# MainShunt.net
KiCad netlist of a schematic drawn in Altium Designer
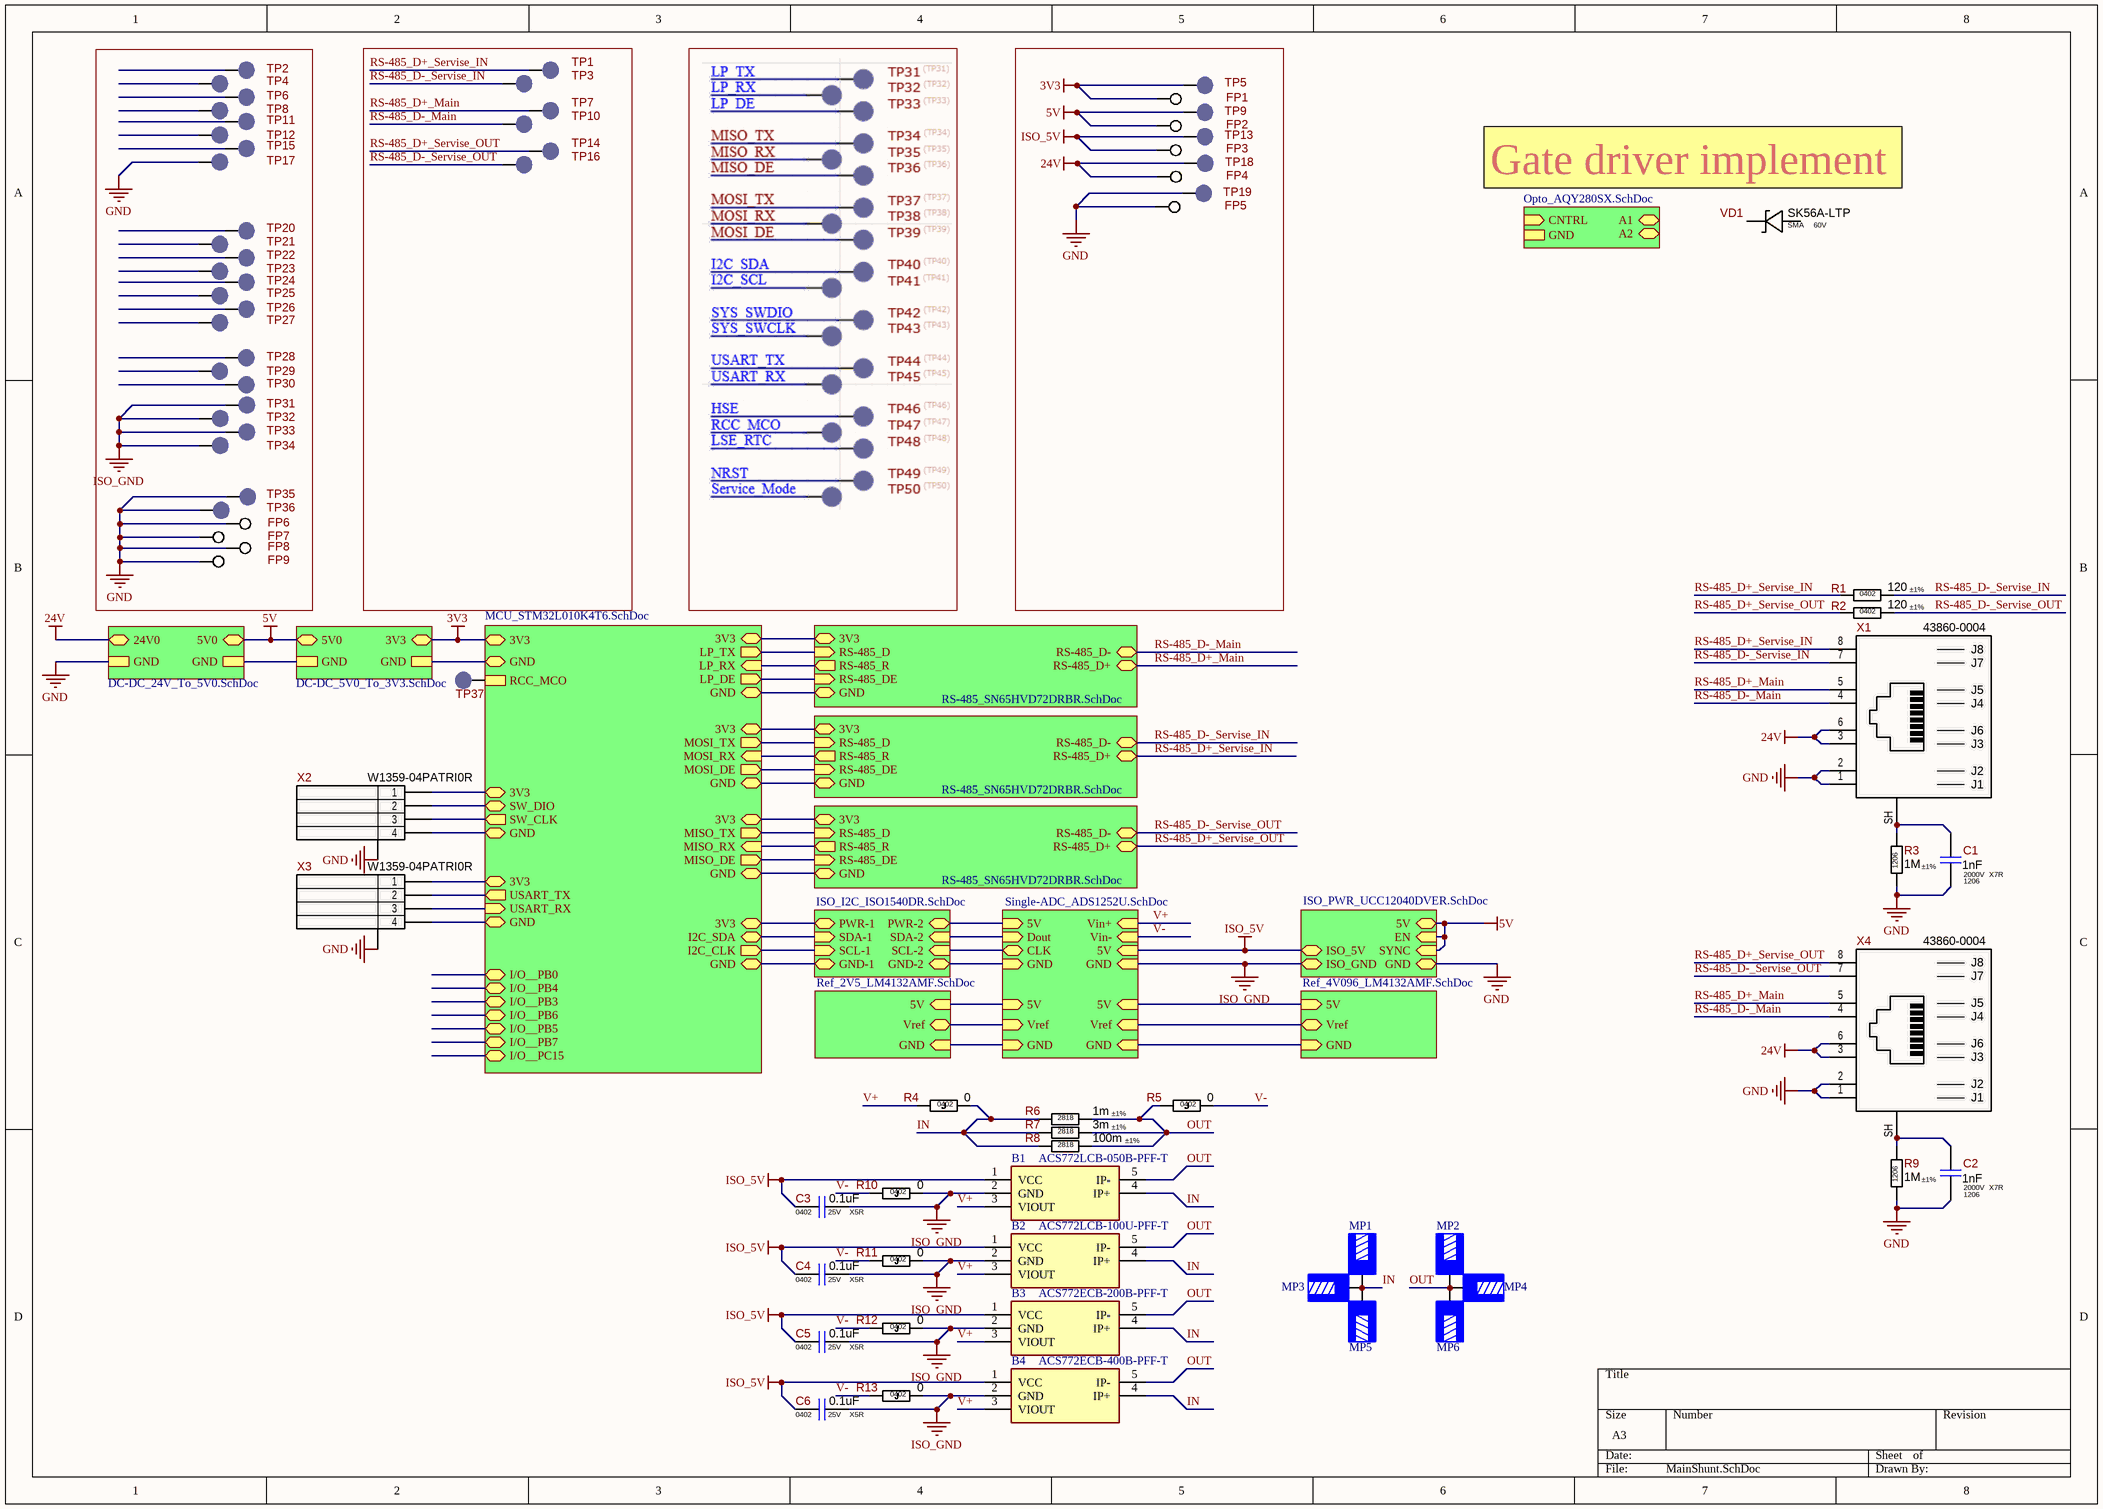
[diagram p0: MainShunt.SchDoc]

(export (version "E")
  (design (tool "Eeschema 10.0.6"))
  (components
    (comp (ref "B1")
      (value "ACS772LCB-050B-PFF-T")
      (footprint "ACS772KCB_XXX_PFF_T")
      (libsource (lib "EL.XXX.T01") (part "ACS772LCB-050B-PFF-T"))
    )
    (comp (ref "B2")
      (value "ACS772LCB-100U-PFF-T")
      (footprint "ACS772KCB_XXX_SMT_T")
      (libsource (lib "EL.XXX.T01") (part "ACS772LCB-100U-PFF-T"))
    )
    (comp (ref "B3")
      (value "ACS772ECB-200B-PFF-T")
      (footprint "ACS772KCB_XXX_PFF_T")
      (libsource (lib "EL.XXX.T01") (part "ACS772ECB-200B-PFF-T"))
    )
    (comp (ref "B4")
      (value "ACS772ECB-400B-PFF-T")
      (footprint "ACS772KCB_XXX_PFF_T")
      (libsource (lib "EL.XXX.T01") (part "ACS772ECB-400B-PFF-T"))
    )
    (comp (ref "C1")
      (value "1nF")
      (footprint "CAP-1206(3216)X125T20")
      (description "1nF 2000V X7R ±10% 1206 Ceramic Capacitor RoHS")
      (fields
        (field (name "PACKAGE") "1206")
        (field (name "VOLTAGE") "2000V")
        (field (name "DIELECTRIC TYPE") "X7R")
        (field (name "PART NUMBER") "CC1206KKX7RDBB102")
        (field (name "MANUFACTURER") "Yageo")
      )
      (libsource (lib "EL.XXX.T01") (part "Capacitor-NonPolar"))
    )
    (comp (ref "C2")
      (value "1nF")
      (footprint "CAP-1206(3216)X125T20")
      (description "1nF 2000V X7R ±10% 1206 Ceramic Capacitor RoHS")
      (fields
        (field (name "PACKAGE") "1206")
        (field (name "VOLTAGE") "2000V")
        (field (name "DIELECTRIC TYPE") "X7R")
        (field (name "PART NUMBER") "CC1206KKX7RDBB102")
        (field (name "MANUFACTURER") "Yageo")
      )
      (libsource (lib "EL.XXX.T01") (part "Capacitor-NonPolar"))
    )
    (comp (ref "C3")
      (value "0.1uF")
      (footprint "C_CERAMIC_0402_MED")
      (description "100nF 25V X5R ±10% 0402 Ceramic Capacitor RoHS")
      (fields
        (field (name "PART NUMBER") "CL05A104KA5NNNC")
        (field (name "MANUFACTURER") "Samsung Electro-Mechanics")
        (field (name "PACKAGE") "0402")
        (field (name "VOLTAGE") "25V")
        (field (name "DIELECTRIC TYPE") "X5R")
      )
      (libsource (lib "EL.XXX.T01") (part "CL05A104KA5NNNC"))
    )
    (comp (ref "C4")
      (value "0.1uF")
      (footprint "C_CERAMIC_0402_MED")
      (description "100nF 25V X5R ±10% 0402 Ceramic Capacitor RoHS")
      (fields
        (field (name "PART NUMBER") "CL05A104KA5NNNC")
        (field (name "MANUFACTURER") "Samsung Electro-Mechanics")
        (field (name "PACKAGE") "0402")
        (field (name "VOLTAGE") "25V")
        (field (name "DIELECTRIC TYPE") "X5R")
      )
      (libsource (lib "EL.XXX.T01") (part "CL05A104KA5NNNC"))
    )
    (comp (ref "C5")
      (value "0.1uF")
      (footprint "C_CERAMIC_0402_MED")
      (description "100nF 25V X5R ±10% 0402 Ceramic Capacitor RoHS")
      (fields
        (field (name "PART NUMBER") "CL05A104KA5NNNC")
        (field (name "MANUFACTURER") "Samsung Electro-Mechanics")
        (field (name "PACKAGE") "0402")
        (field (name "VOLTAGE") "25V")
        (field (name "DIELECTRIC TYPE") "X5R")
      )
      (libsource (lib "EL.XXX.T01") (part "CL05A104KA5NNNC"))
    )
    (comp (ref "C6")
      (value "0.1uF")
      (footprint "C_CERAMIC_0402_MED")
      (description "100nF 25V X5R ±10% 0402 Ceramic Capacitor RoHS")
      (fields
        (field (name "PART NUMBER") "CL05A104KA5NNNC")
        (field (name "MANUFACTURER") "Samsung Electro-Mechanics")
        (field (name "PACKAGE") "0402")
        (field (name "VOLTAGE") "25V")
        (field (name "DIELECTRIC TYPE") "X5R")
      )
      (libsource (lib "EL.XXX.T01") (part "CL05A104KA5NNNC"))
    )
    (comp (ref "FP1")
      (value "PAD-1.1mm")
      (footprint "PAD-1.1mm")
      (description "1.1mm Pad for Plug-In or Receptacle")
      (fields (field (name "MANUFACTURER") "NONE"))
      (libsource (lib "EL.XXX.T01") (part "Pad"))
    )
    (comp (ref "FP2")
      (value "PAD-1.1mm")
      (footprint "PAD-1.1mm")
      (description "1.1mm Pad for Plug-In or Receptacle")
      (fields (field (name "MANUFACTURER") "NONE"))
      (libsource (lib "EL.XXX.T01") (part "Pad"))
    )
    (comp (ref "FP3")
      (value "PAD-1.1mm")
      (footprint "PAD-1.1mm")
      (description "1.1mm Pad for Plug-In or Receptacle")
      (fields (field (name "MANUFACTURER") "NONE"))
      (libsource (lib "EL.XXX.T01") (part "Pad"))
    )
    (comp (ref "FP4")
      (value "PAD-1.1mm")
      (footprint "PAD-1.1mm")
      (description "1.1mm Pad for Plug-In or Receptacle")
      (fields (field (name "MANUFACTURER") "NONE"))
      (libsource (lib "EL.XXX.T01") (part "Pad"))
    )
    (comp (ref "FP5")
      (value "PAD-1.1mm")
      (footprint "PAD-1.1mm")
      (description "1.1mm Pad for Plug-In or Receptacle")
      (fields (field (name "MANUFACTURER") "NONE"))
      (libsource (lib "EL.XXX.T01") (part "Pad"))
    )
    (comp (ref "FP6")
      (value "PAD-1.1mm")
      (footprint "PAD-1.1mm")
      (description "1.1mm Pad for Plug-In or Receptacle")
      (fields (field (name "MANUFACTURER") "NONE"))
      (libsource (lib "EL.XXX.T01") (part "Pad"))
    )
    (comp (ref "FP7")
      (value "PAD-1.1mm")
      (footprint "PAD-1.1mm")
      (description "1.1mm Pad for Plug-In or Receptacle")
      (fields (field (name "MANUFACTURER") "NONE"))
      (libsource (lib "EL.XXX.T01") (part "Pad"))
    )
    (comp (ref "FP8")
      (value "PAD-1.1mm")
      (footprint "PAD-1.1mm")
      (description "1.1mm Pad for Plug-In or Receptacle")
      (fields (field (name "MANUFACTURER") "NONE"))
      (libsource (lib "EL.XXX.T01") (part "Pad"))
    )
    (comp (ref "FP9")
      (value "PAD-1.1mm")
      (footprint "PAD-1.1mm")
      (description "1.1mm Pad for Plug-In or Receptacle")
      (fields (field (name "MANUFACTURER") "NONE"))
      (libsource (lib "EL.XXX.T01") (part "Pad"))
    )
    (comp (ref "MP1")
      (value "M6 x 9mm")
      (footprint "7461084_HAL")
      (description "WP-BUTR REDCUBE PRESS-FIT with internal thread, two-rows, L10W10H13.5mm, M6 x 9mm, 160A")
      (fields
        (field (name "MANUFACTURER PART NUMBER") "7461084")
        (field (name "MANUFACTURER") "Wurth Elektronik")
      )
      (libsource (lib "EL.XXX.T01") (part "7461084"))
    )
    (comp (ref "MP2")
      (value "M6 x 9mm")
      (footprint "7461084_HAL")
      (description "WP-BUTR REDCUBE PRESS-FIT with internal thread, two-rows, L10W10H13.5mm, M6 x 9mm, 160A")
      (fields
        (field (name "MANUFACTURER PART NUMBER") "7461084")
        (field (name "MANUFACTURER") "Wurth Elektronik")
      )
      (libsource (lib "EL.XXX.T01") (part "7461084"))
    )
    (comp (ref "MP3")
      (value "M6 x 9mm")
      (footprint "7461084_HAL")
      (description "WP-BUTR REDCUBE PRESS-FIT with internal thread, two-rows, L10W10H13.5mm, M6 x 9mm, 160A")
      (fields
        (field (name "MANUFACTURER PART NUMBER") "7461084")
        (field (name "MANUFACTURER") "Wurth Elektronik")
      )
      (libsource (lib "EL.XXX.T01") (part "7461084"))
    )
    (comp (ref "MP4")
      (value "M6 x 9mm")
      (footprint "7461084_HAL")
      (description "WP-BUTR REDCUBE PRESS-FIT with internal thread, two-rows, L10W10H13.5mm, M6 x 9mm, 160A")
      (fields
        (field (name "MANUFACTURER PART NUMBER") "7461084")
        (field (name "MANUFACTURER") "Wurth Elektronik")
      )
      (libsource (lib "EL.XXX.T01") (part "7461084"))
    )
    (comp (ref "MP5")
      (value "M6 x 9mm")
      (footprint "7461084_HAL")
      (description "WP-BUTR REDCUBE PRESS-FIT with internal thread, two-rows, L10W10H13.5mm, M6 x 9mm, 160A")
      (fields
        (field (name "MANUFACTURER PART NUMBER") "7461084")
        (field (name "MANUFACTURER") "Wurth Elektronik")
      )
      (libsource (lib "EL.XXX.T01") (part "7461084"))
    )
    (comp (ref "MP6")
      (value "M6 x 9mm")
      (footprint "7461084_HAL")
      (description "WP-BUTR REDCUBE PRESS-FIT with internal thread, two-rows, L10W10H13.5mm, M6 x 9mm, 160A")
      (fields
        (field (name "MANUFACTURER PART NUMBER") "7461084")
        (field (name "MANUFACTURER") "Wurth Elektronik")
      )
      (libsource (lib "EL.XXX.T01") (part "7461084"))
    )
    (comp (ref "R1")
      (value "120")
      (footprint "R_ANY_CHIP_0402_HI")
      (description "120 Ohms ±1% 1/16W 0402 Thick Film Resistor")
      (fields
        (field (name "TOLERANCE") "±1%")
        (field (name "PACKAGE") "0402")
        (field (name "PART NUMBER") "RC0402FR-07120RL")
        (field (name "MANUFACTURER") "Yageo")
      )
      (libsource (lib "EL.XXX.T01") (part "Resistor"))
    )
    (comp (ref "R2")
      (value "120")
      (footprint "R_ANY_CHIP_0402_HI")
      (description "120 Ohms ±1% 1/16W 0402 Thick Film Resistor")
      (fields
        (field (name "TOLERANCE") "±1%")
        (field (name "PACKAGE") "0402")
        (field (name "PART NUMBER") "RC0402FR-07120RL")
        (field (name "MANUFACTURER") "Yageo")
      )
      (libsource (lib "EL.XXX.T01") (part "Resistor"))
    )
    (comp (ref "R3")
      (value "1M")
      (footprint "CHV1206-Series")
      (description "1 MOhms ±1%, 1/4W 1206 Thick Film Resistor")
      (fields
        (field (name "TOLERANCE") "±1%")
        (field (name "PACKAGE") "1206")
        (field (name "PART NUMBER") "CHV1206-FX-1004ELF")
        (field (name "MANUFACTURER") "Bourns")
      )
      (libsource (lib "EL.XXX.T01") (part "Resistor"))
    )
    (comp (ref "R4")
      (value "0")
      (footprint "R_ANY_CHIP_0402_HI")
      (description "0 Ohms Jumper ±5% 1/16W 0402 Thick Film Resistor")
      (fields
        (field (name "TOLERANCE") "±5%")
        (field (name "PART NUMBER") "RC0402JR-070RL")
        (field (name "PACKAGE") "0402")
      )
      (libsource (lib "EL.XXX.T01") (part "RC0402JR-070RL"))
    )
    (comp (ref "R5")
      (value "0")
      (footprint "R_ANY_CHIP_0402_HI")
      (description "0 Ohms Jumper ±5% 1/16W 0402 Thick Film Resistor")
      (fields
        (field (name "TOLERANCE") "±5%")
        (field (name "PART NUMBER") "RC0402JR-070RL")
        (field (name "PACKAGE") "0402")
      )
      (libsource (lib "EL.XXX.T01") (part "RC0402JR-070RL"))
    )
    (comp (ref "R6")
      (value "1m")
      (footprint "WSHP2818")
      (description "Current Sense Resistors - SMD 10W .001ohms 1%")
      (fields
        (field (name "PART NUMBER") "WSHP28181L000FEA")
        (field (name "MANUFACTURER") "Vishay")
        (field (name "TOLERANCE") "±1%")
        (field (name "PACKAGE") "2818")
      )
      (libsource (lib "EL.XXX.T01") (part "WSHP28181L000FEA"))
    )
    (comp (ref "R7")
      (value "3m")
      (footprint "WSHP2818")
      (description "Current Sense Resistors - SMD 10W .003ohms 1%")
      (fields
        (field (name "PART NUMBER") "WSHP28183L000FEA")
        (field (name "MANUFACTURER") "Vishay")
        (field (name "TOLERANCE") "±1%")
        (field (name "PACKAGE") "2818")
      )
      (libsource (lib "EL.XXX.T01") (part "WSHP28183L000FEA"))
    )
    (comp (ref "R8")
      (value "100m")
      (footprint "WSHP2818")
      (description "Current Sense Resistors - SMD 10W .100ohms 1%")
      (fields
        (field (name "PART NUMBER") "WSHP2818R1000FEA")
        (field (name "MANUFACTURER") "Vishay")
        (field (name "TOLERANCE") "±1%")
        (field (name "PACKAGE") "2818")
      )
      (libsource (lib "EL.XXX.T01") (part "WSHP2818R1000FEA"))
    )
    (comp (ref "R9")
      (value "1M")
      (footprint "CHV1206-Series")
      (description "1 MOhms ±1%, 1/4W 1206 Thick Film Resistor")
      (fields
        (field (name "TOLERANCE") "±1%")
        (field (name "PACKAGE") "1206")
        (field (name "PART NUMBER") "CHV1206-FX-1004ELF")
        (field (name "MANUFACTURER") "Bourns")
      )
      (libsource (lib "EL.XXX.T01") (part "Resistor"))
    )
    (comp (ref "R10")
      (value "0")
      (footprint "R_ANY_CHIP_0402_HI")
      (description "0 Ohms Jumper ±5% 1/16W 0402 Thick Film Resistor")
      (fields
        (field (name "TOLERANCE") "±5%")
        (field (name "PART NUMBER") "RC0402JR-070RL")
        (field (name "PACKAGE") "0402")
      )
      (libsource (lib "EL.XXX.T01") (part "RC0402JR-070RL"))
    )
    (comp (ref "R11")
      (value "0")
      (footprint "R_ANY_CHIP_0402_HI")
      (description "0 Ohms Jumper ±5% 1/16W 0402 Thick Film Resistor")
      (fields
        (field (name "TOLERANCE") "±5%")
        (field (name "PART NUMBER") "RC0402JR-070RL")
        (field (name "PACKAGE") "0402")
      )
      (libsource (lib "EL.XXX.T01") (part "RC0402JR-070RL"))
    )
    (comp (ref "R12")
      (value "0")
      (footprint "R_ANY_CHIP_0402_HI")
      (description "0 Ohms Jumper ±5% 1/16W 0402 Thick Film Resistor")
      (fields
        (field (name "TOLERANCE") "±5%")
        (field (name "PART NUMBER") "RC0402JR-070RL")
        (field (name "PACKAGE") "0402")
      )
      (libsource (lib "EL.XXX.T01") (part "RC0402JR-070RL"))
    )
    (comp (ref "R13")
      (value "0")
      (footprint "R_ANY_CHIP_0402_HI")
      (description "0 Ohms Jumper ±5% 1/16W 0402 Thick Film Resistor")
      (fields
        (field (name "TOLERANCE") "±5%")
        (field (name "PART NUMBER") "RC0402JR-070RL")
        (field (name "PACKAGE") "0402")
      )
      (libsource (lib "EL.XXX.T01") (part "RC0402JR-070RL"))
    )
    (comp (ref "TP1")
      (value "LED_LINK")
      (footprint "TP_SMD_2mm")
      (description "Test Point SMD Pad 1.0mm/1.5mm/2mm")
      (fields (field (name "PART NUMBER") "TP-PAD-SMD"))
      (libsource (lib "EL.XXX.T01") (part "Test-Point-SMD-1"))
    )
    (comp (ref "TP2")
      (value "LED_LINK")
      (footprint "TP_SMD_2mm")
      (description "Test Point SMD Pad 1.0mm/1.5mm/2mm")
      (fields (field (name "PART NUMBER") "TP-PAD-SMD"))
      (libsource (lib "EL.XXX.T01") (part "Test-Point-SMD-1"))
    )
    (comp (ref "TP3")
      (value "LED_LINK")
      (footprint "TP_SMD_2mm")
      (description "Test Point SMD Pad 1.0mm/1.5mm/2mm")
      (fields (field (name "PART NUMBER") "TP-PAD-SMD"))
      (libsource (lib "EL.XXX.T01") (part "Test-Point-SMD-1"))
    )
    (comp (ref "TP4")
      (value "LED_LINK")
      (footprint "TP_SMD_2mm")
      (description "Test Point SMD Pad 1.0mm/1.5mm/2mm")
      (fields (field (name "PART NUMBER") "TP-PAD-SMD"))
      (libsource (lib "EL.XXX.T01") (part "Test-Point-SMD-1"))
    )
    (comp (ref "TP5")
      (value "LED_LINK")
      (footprint "TP_SMD_2mm")
      (description "Test Point SMD Pad 1.0mm/1.5mm/2mm")
      (fields (field (name "PART NUMBER") "TP-PAD-SMD"))
      (libsource (lib "EL.XXX.T01") (part "Test-Point-SMD-1"))
    )
    (comp (ref "TP6")
      (value "LED_LINK")
      (footprint "TP_SMD_2mm")
      (description "Test Point SMD Pad 1.0mm/1.5mm/2mm")
      (fields (field (name "PART NUMBER") "TP-PAD-SMD"))
      (libsource (lib "EL.XXX.T01") (part "Test-Point-SMD-1"))
    )
    (comp (ref "TP7")
      (value "LED_LINK")
      (footprint "TP_SMD_2mm")
      (description "Test Point SMD Pad 1.0mm/1.5mm/2mm")
      (fields (field (name "PART NUMBER") "TP-PAD-SMD"))
      (libsource (lib "EL.XXX.T01") (part "Test-Point-SMD-1"))
    )
    (comp (ref "TP8")
      (value "LED_LINK")
      (footprint "TP_SMD_2mm")
      (description "Test Point SMD Pad 1.0mm/1.5mm/2mm")
      (fields (field (name "PART NUMBER") "TP-PAD-SMD"))
      (libsource (lib "EL.XXX.T01") (part "Test-Point-SMD-1"))
    )
    (comp (ref "TP9")
      (value "LED_LINK")
      (footprint "TP_SMD_2mm")
      (description "Test Point SMD Pad 1.0mm/1.5mm/2mm")
      (fields (field (name "PART NUMBER") "TP-PAD-SMD"))
      (libsource (lib "EL.XXX.T01") (part "Test-Point-SMD-1"))
    )
    (comp (ref "TP10")
      (value "LED_LINK")
      (footprint "TP_SMD_2mm")
      (description "Test Point SMD Pad 1.0mm/1.5mm/2mm")
      (fields (field (name "PART NUMBER") "TP-PAD-SMD"))
      (libsource (lib "EL.XXX.T01") (part "Test-Point-SMD-1"))
    )
    (comp (ref "TP11")
      (value "LED_LINK")
      (footprint "TP_SMD_2mm")
      (description "Test Point SMD Pad 1.0mm/1.5mm/2mm")
      (fields (field (name "PART NUMBER") "TP-PAD-SMD"))
      (libsource (lib "EL.XXX.T01") (part "Test-Point-SMD-1"))
    )
    (comp (ref "TP12")
      (value "LED_LINK")
      (footprint "TP_SMD_2mm")
      (description "Test Point SMD Pad 1.0mm/1.5mm/2mm")
      (fields (field (name "PART NUMBER") "TP-PAD-SMD"))
      (libsource (lib "EL.XXX.T01") (part "Test-Point-SMD-1"))
    )
    (comp (ref "TP13")
      (value "LED_LINK")
      (footprint "TP_SMD_2mm")
      (description "Test Point SMD Pad 1.0mm/1.5mm/2mm")
      (fields (field (name "PART NUMBER") "TP-PAD-SMD"))
      (libsource (lib "EL.XXX.T01") (part "Test-Point-SMD-1"))
    )
    (comp (ref "TP14")
      (value "LED_LINK")
      (footprint "TP_SMD_2mm")
      (description "Test Point SMD Pad 1.0mm/1.5mm/2mm")
      (fields (field (name "PART NUMBER") "TP-PAD-SMD"))
      (libsource (lib "EL.XXX.T01") (part "Test-Point-SMD-1"))
    )
    (comp (ref "TP15")
      (value "LED_LINK")
      (footprint "TP_SMD_2mm")
      (description "Test Point SMD Pad 1.0mm/1.5mm/2mm")
      (fields (field (name "PART NUMBER") "TP-PAD-SMD"))
      (libsource (lib "EL.XXX.T01") (part "Test-Point-SMD-1"))
    )
    (comp (ref "TP16")
      (value "LED_LINK")
      (footprint "TP_SMD_2mm")
      (description "Test Point SMD Pad 1.0mm/1.5mm/2mm")
      (fields (field (name "PART NUMBER") "TP-PAD-SMD"))
      (libsource (lib "EL.XXX.T01") (part "Test-Point-SMD-1"))
    )
    (comp (ref "TP17")
      (value "LED_LINK")
      (footprint "TP_SMD_2mm")
      (description "Test Point SMD Pad 1.0mm/1.5mm/2mm")
      (fields (field (name "PART NUMBER") "TP-PAD-SMD"))
      (libsource (lib "EL.XXX.T01") (part "Test-Point-SMD-1"))
    )
    (comp (ref "TP18")
      (value "LED_LINK")
      (footprint "TP_SMD_2mm")
      (description "Test Point SMD Pad 1.0mm/1.5mm/2mm")
      (fields (field (name "PART NUMBER") "TP-PAD-SMD"))
      (libsource (lib "EL.XXX.T01") (part "Test-Point-SMD-1"))
    )
    (comp (ref "TP19")
      (value "LED_LINK")
      (footprint "TP_SMD_2mm")
      (description "Test Point SMD Pad 1.0mm/1.5mm/2mm")
      (fields (field (name "PART NUMBER") "TP-PAD-SMD"))
      (libsource (lib "EL.XXX.T01") (part "Test-Point-SMD-1"))
    )
    (comp (ref "TP20")
      (value "LED_LINK")
      (footprint "TP_SMD_2mm")
      (description "Test Point SMD Pad 1.0mm/1.5mm/2mm")
      (fields (field (name "PART NUMBER") "TP-PAD-SMD"))
      (libsource (lib "EL.XXX.T01") (part "Test-Point-SMD-1"))
    )
    (comp (ref "TP21")
      (value "LED_LINK")
      (footprint "TP_SMD_2mm")
      (description "Test Point SMD Pad 1.0mm/1.5mm/2mm")
      (fields (field (name "PART NUMBER") "TP-PAD-SMD"))
      (libsource (lib "EL.XXX.T01") (part "Test-Point-SMD-1"))
    )
    (comp (ref "TP22")
      (value "LED_LINK")
      (footprint "TP_SMD_2mm")
      (description "Test Point SMD Pad 1.0mm/1.5mm/2mm")
      (fields (field (name "PART NUMBER") "TP-PAD-SMD"))
      (libsource (lib "EL.XXX.T01") (part "Test-Point-SMD-1"))
    )
    (comp (ref "TP23")
      (value "LED_LINK")
      (footprint "TP_SMD_2mm")
      (description "Test Point SMD Pad 1.0mm/1.5mm/2mm")
      (fields (field (name "PART NUMBER") "TP-PAD-SMD"))
      (libsource (lib "EL.XXX.T01") (part "Test-Point-SMD-1"))
    )
    (comp (ref "TP24")
      (value "LED_LINK")
      (footprint "TP_SMD_2mm")
      (description "Test Point SMD Pad 1.0mm/1.5mm/2mm")
      (fields (field (name "PART NUMBER") "TP-PAD-SMD"))
      (libsource (lib "EL.XXX.T01") (part "Test-Point-SMD-1"))
    )
    (comp (ref "TP25")
      (value "LED_LINK")
      (footprint "TP_SMD_2mm")
      (description "Test Point SMD Pad 1.0mm/1.5mm/2mm")
      (fields (field (name "PART NUMBER") "TP-PAD-SMD"))
      (libsource (lib "EL.XXX.T01") (part "Test-Point-SMD-1"))
    )
    (comp (ref "TP26")
      (value "LED_LINK")
      (footprint "TP_SMD_2mm")
      (description "Test Point SMD Pad 1.0mm/1.5mm/2mm")
      (fields (field (name "PART NUMBER") "TP-PAD-SMD"))
      (libsource (lib "EL.XXX.T01") (part "Test-Point-SMD-1"))
    )
    (comp (ref "TP27")
      (value "LED_LINK")
      (footprint "TP_SMD_2mm")
      (description "Test Point SMD Pad 1.0mm/1.5mm/2mm")
      (fields (field (name "PART NUMBER") "TP-PAD-SMD"))
      (libsource (lib "EL.XXX.T01") (part "Test-Point-SMD-1"))
    )
    (comp (ref "TP28")
      (value "LED_LINK")
      (footprint "TP_SMD_2mm")
      (description "Test Point SMD Pad 1.0mm/1.5mm/2mm")
      (fields (field (name "PART NUMBER") "TP-PAD-SMD"))
      (libsource (lib "EL.XXX.T01") (part "Test-Point-SMD-1"))
    )
    (comp (ref "TP29")
      (value "LED_LINK")
      (footprint "TP_SMD_2mm")
      (description "Test Point SMD Pad 1.0mm/1.5mm/2mm")
      (fields (field (name "PART NUMBER") "TP-PAD-SMD"))
      (libsource (lib "EL.XXX.T01") (part "Test-Point-SMD-1"))
    )
    (comp (ref "TP30")
      (value "LED_LINK")
      (footprint "TP_SMD_2mm")
      (description "Test Point SMD Pad 1.0mm/1.5mm/2mm")
      (fields (field (name "PART NUMBER") "TP-PAD-SMD"))
      (libsource (lib "EL.XXX.T01") (part "Test-Point-SMD-1"))
    )
    (comp (ref "TP31")
      (value "LED_LINK")
      (footprint "TP_SMD_2mm")
      (description "Test Point SMD Pad 1.0mm/1.5mm/2mm")
      (fields (field (name "PART NUMBER") "TP-PAD-SMD"))
      (libsource (lib "EL.XXX.T01") (part "Test-Point-SMD-1"))
    )
    (comp (ref "TP32")
      (value "LED_LINK")
      (footprint "TP_SMD_2mm")
      (description "Test Point SMD Pad 1.0mm/1.5mm/2mm")
      (fields (field (name "PART NUMBER") "TP-PAD-SMD"))
      (libsource (lib "EL.XXX.T01") (part "Test-Point-SMD-1"))
    )
    (comp (ref "TP33")
      (value "LED_LINK")
      (footprint "TP_SMD_2mm")
      (description "Test Point SMD Pad 1.0mm/1.5mm/2mm")
      (fields (field (name "PART NUMBER") "TP-PAD-SMD"))
      (libsource (lib "EL.XXX.T01") (part "Test-Point-SMD-1"))
    )
    (comp (ref "TP34")
      (value "LED_LINK")
      (footprint "TP_SMD_2mm")
      (description "Test Point SMD Pad 1.0mm/1.5mm/2mm")
      (fields (field (name "PART NUMBER") "TP-PAD-SMD"))
      (libsource (lib "EL.XXX.T01") (part "Test-Point-SMD-1"))
    )
    (comp (ref "TP35")
      (value "LED_LINK")
      (footprint "TP_SMD_2mm")
      (description "Test Point SMD Pad 1.0mm/1.5mm/2mm")
      (fields (field (name "PART NUMBER") "TP-PAD-SMD"))
      (libsource (lib "EL.XXX.T01") (part "Test-Point-SMD-1"))
    )
    (comp (ref "TP36")
      (value "LED_LINK")
      (footprint "TP_SMD_2mm")
      (description "Test Point SMD Pad 1.0mm/1.5mm/2mm")
      (fields (field (name "PART NUMBER") "TP-PAD-SMD"))
      (libsource (lib "EL.XXX.T01") (part "Test-Point-SMD-1"))
    )
    (comp (ref "TP37")
      (value "LED_LINK")
      (footprint "TP_SMD_2mm")
      (description "Test Point SMD Pad 1.0mm/1.5mm/2mm")
      (fields (field (name "PART NUMBER") "TP-PAD-SMD"))
      (libsource (lib "EL.XXX.T01") (part "Test-Point-SMD-1"))
    )
    (comp (ref "VD1")
      (value "SK56A-LTP")
      (footprint "SMA_MED")
      (description "Diode Schottky 60V 5A, SMA")
      (fields
        (field (name "MANUFACTURER") "Micro Commercial Components")
        (field (name "PART NUMBER") "SK56A-LTP")
        (field (name "PACKAGE") "SMA")
        (field (name "VOLTAGE") "60V")
      )
      (libsource (lib "EL.XXX.T01") (part "SK56A-LTP"))
    )
    (comp (ref "X1")
      (value "43860-0004")
      (footprint "43860-0004")
      (description "RJ45 8P8C Shielded Cat 3 10 Base-T Connector")
      (fields (field (name "PART NUMBER") "43860-0004") (field (name "MANUFACTURER") "Molex"))
      (libsource (lib "EL.XXX.T01") (part "43860-0004"))
    )
    (comp (ref "X2")
      (value "W1359-04PATRI0R")
      (footprint "W1359-04PATXI0R_DBG")
      (description "1.25mm Wire-to-Board Header, Vertical, SMT, 4 pin")
      (fields
        (field (name "PART NUMBER") "W1359-04PATRI0R")
        (field (name "MANUFACTURER") "Hsuan Mao Technology")
      )
      (libsource (lib "EL.XXX.T01") (part "General-4-Pin-MP"))
    )
    (comp (ref "X3")
      (value "W1359-04PATRI0R")
      (footprint "W1359-04PATXI0R_DBG")
      (description "1.25mm Wire-to-Board Header, Vertical, SMT, 4 pin")
      (fields
        (field (name "PART NUMBER") "W1359-04PATRI0R")
        (field (name "MANUFACTURER") "Hsuan Mao Technology")
      )
      (libsource (lib "EL.XXX.T01") (part "General-4-Pin-MP"))
    )
    (comp (ref "X4")
      (value "43860-0004")
      (footprint "43860-0004")
      (description "RJ45 8P8C Shielded Cat 3 10 Base-T Connector")
      (fields (field (name "PART NUMBER") "43860-0004") (field (name "MANUFACTURER") "Molex"))
      (libsource (lib "EL.XXX.T01") (part "43860-0004"))
    )
  )
  (nets
    (net (code "2") (name "/3V3_1") (class "Default")
      (node (ref "X2") (pin "1") (pinfunction "1_1") (pintype "passive"))
    )
    (net (code "3") (name "/3V3_2") (class "Default")
      (node (ref "X3") (pin "1") (pinfunction "1_1") (pintype "passive"))
    )
    (net (code "21") (name "/GND_3") (class "Default")
      (node (ref "X2") (pin "4") (pinfunction "4_4") (pintype "passive"))
    )
    (net (code "22") (name "/GND_4") (class "Default")
      (node (ref "X3") (pin "4") (pinfunction "4_4") (pintype "passive"))
    )
    (net (code "35") (name "/IN") (class "Default")
      (node (ref "B1") (pin "4") (pinfunction "IP+_4") (pintype "passive"))
      (node (ref "B2") (pin "4") (pinfunction "IP+_4") (pintype "passive"))
      (node (ref "B3") (pin "4") (pinfunction "IP+_4") (pintype "passive"))
      (node (ref "B4") (pin "4") (pinfunction "IP+_4") (pintype "passive"))
      (node (ref "MP1") (pin "1") (pinfunction "1_1") (pintype "passive"))
      (node (ref "MP3") (pin "1") (pinfunction "1_1") (pintype "passive"))
      (node (ref "MP5") (pin "1") (pinfunction "1_1") (pintype "passive"))
      (node (ref "R4") (pin "1") (pintype "passive"))
      (node (ref "R6") (pin "2") (pintype "passive"))
      (node (ref "R7") (pin "2") (pintype "passive"))
      (node (ref "R8") (pin "2") (pintype "passive"))
    )
    (net (code "52") (name "/OUT") (class "Default")
      (node (ref "B1") (pin "5") (pinfunction "IP-_5") (pintype "passive"))
      (node (ref "B2") (pin "5") (pinfunction "IP-_5") (pintype "passive"))
      (node (ref "B3") (pin "5") (pinfunction "IP-_5") (pintype "passive"))
      (node (ref "B4") (pin "5") (pinfunction "IP-_5") (pintype "passive"))
      (node (ref "MP2") (pin "1") (pinfunction "1_1") (pintype "passive"))
      (node (ref "MP4") (pin "1") (pinfunction "1_1") (pintype "passive"))
      (node (ref "MP6") (pin "1") (pinfunction "1_1") (pintype "passive"))
      (node (ref "R5") (pin "2") (pintype "passive"))
      (node (ref "R6") (pin "1") (pintype "passive"))
      (node (ref "R7") (pin "1") (pintype "passive"))
      (node (ref "R8") (pin "1") (pintype "passive"))
    )
    (net (code "53") (name "/RCC_MCO") (class "Default") (node (ref "TP37") (pin "1") (pintype "passive")))
    (net (code "55") (name "/RS-485_D+_Main") (class "Default")
      (node (ref "TP7") (pin "1") (pintype "passive"))
      (node (ref "X1") (pin "5") (pinfunction "CT_5") (pintype "passive"))
      (node (ref "X4") (pin "5") (pinfunction "CT_5") (pintype "passive"))
    )
    (net (code "56") (name "/RS-485_D+_Servise_IN") (class "Default")
      (node (ref "R1") (pin "1") (pintype "passive"))
      (node (ref "TP1") (pin "1") (pintype "passive"))
      (node (ref "X1") (pin "8") (pinfunction "TD2+_8") (pintype "passive"))
    )
    (net (code "57") (name "/RS-485_D+_Servise_OUT") (class "Default")
      (node (ref "R2") (pin "1") (pintype "passive"))
      (node (ref "TP14") (pin "1") (pintype "passive"))
      (node (ref "X4") (pin "8") (pinfunction "TD2+_8") (pintype "passive"))
    )
    (net (code "58") (name "/RS-485_D-_Main") (class "Default")
      (node (ref "TP10") (pin "1") (pintype "passive"))
      (node (ref "X1") (pin "4") (pinfunction "TD3+_4") (pintype "passive"))
      (node (ref "X4") (pin "4") (pinfunction "TD3+_4") (pintype "passive"))
    )
    (net (code "59") (name "/RS-485_D-_Servise_IN") (class "Default")
      (node (ref "R1") (pin "2") (pintype "passive"))
      (node (ref "TP3") (pin "1") (pintype "passive"))
      (node (ref "X1") (pin "7") (pinfunction "TD2-_7") (pintype "passive"))
    )
    (net (code "60") (name "/RS-485_D-_Servise_OUT") (class "Default")
      (node (ref "R2") (pin "2") (pintype "passive"))
      (node (ref "TP16") (pin "1") (pintype "passive"))
      (node (ref "X4") (pin "7") (pinfunction "TD2-_7") (pintype "passive"))
    )
    (net (code "69") (name "/SW_CLK") (class "Default")
      (node (ref "X2") (pin "3") (pinfunction "3_3") (pintype "passive"))
    )
    (net (code "70") (name "/SW_DIO") (class "Default")
      (node (ref "X2") (pin "2") (pinfunction "2_2") (pintype "passive"))
    )
    (net (code "71") (name "/USART_RX") (class "Default")
      (node (ref "X3") (pin "3") (pinfunction "3_3") (pintype "passive"))
    )
    (net (code "72") (name "/USART_TX") (class "Default")
      (node (ref "X3") (pin "2") (pinfunction "2_2") (pintype "passive"))
    )
    (net (code "73") (name "/V+") (class "Default")
      (node (ref "B1") (pin "3") (pinfunction "VIOUT_3") (pintype "passive"))
      (node (ref "B2") (pin "3") (pinfunction "VIOUT_3") (pintype "passive"))
      (node (ref "B3") (pin "3") (pinfunction "VIOUT_3") (pintype "passive"))
      (node (ref "B4") (pin "3") (pinfunction "VIOUT_3") (pintype "passive"))
      (node (ref "R4") (pin "2") (pintype "passive"))
    )
    (net (code "74") (name "/V-") (class "Default")
      (node (ref "R10") (pin "2") (pintype "passive"))
      (node (ref "R11") (pin "2") (pintype "passive"))
      (node (ref "R12") (pin "2") (pintype "passive"))
      (node (ref "R13") (pin "2") (pintype "passive"))
      (node (ref "R5") (pin "1") (pintype "passive"))
    )
    (net (code "77") (name "3V3") (class "Default")
      (node (ref "FP1") (pin "1") (pintype "passive"))
      (node (ref "TP5") (pin "1") (pintype "passive"))
    )
    (net (code "78") (name "5V") (class "Default")
      (node (ref "FP2") (pin "1") (pintype "passive"))
      (node (ref "TP9") (pin "1") (pintype "passive"))
    )
    (net (code "79") (name "24V") (class "Default")
      (node (ref "FP4") (pin "1") (pintype "passive"))
      (node (ref "TP18") (pin "1") (pintype "passive"))
      (node (ref "X1") (pin "3") (pinfunction "TD3-_3") (pintype "passive"))
      (node (ref "X1") (pin "6") (pinfunction "CT_6") (pintype "passive"))
      (node (ref "X4") (pin "3") (pinfunction "TD3-_3") (pintype "passive"))
      (node (ref "X4") (pin "6") (pinfunction "CT_6") (pintype "passive"))
    )
    (net (code "80") (name "GND") (class "Default")
      (node (ref "C1") (pin "2") (pinfunction "2_2") (pintype "passive"))
      (node (ref "C2") (pin "2") (pinfunction "2_2") (pintype "passive"))
      (node (ref "FP5") (pin "1") (pintype "passive"))
      (node (ref "FP6") (pin "1") (pintype "passive"))
      (node (ref "FP7") (pin "1") (pintype "passive"))
      (node (ref "FP8") (pin "1") (pintype "passive"))
      (node (ref "FP9") (pin "1") (pintype "passive"))
      (node (ref "R3") (pin "2") (pintype "passive"))
      (node (ref "R9") (pin "2") (pintype "passive"))
      (node (ref "TP17") (pin "1") (pintype "passive"))
      (node (ref "TP19") (pin "1") (pintype "passive"))
      (node (ref "TP35") (pin "1") (pintype "passive"))
      (node (ref "TP36") (pin "1") (pintype "passive"))
      (node (ref "X1") (pin "1") (pinfunction "TD4-_1") (pintype "passive"))
      (node (ref "X1") (pin "2") (pinfunction "TD4+_2") (pintype "passive"))
      (node (ref "X2") (pin "MP") (pinfunction "MountPad_MP") (pintype "passive"))
      (node (ref "X3") (pin "MP") (pinfunction "MountPad_MP") (pintype "passive"))
      (node (ref "X4") (pin "1") (pinfunction "TD4-_1") (pintype "passive"))
      (node (ref "X4") (pin "2") (pinfunction "TD4+_2") (pintype "passive"))
    )
    (net (code "81") (name "ISO_5V") (class "Default")
      (node (ref "B1") (pin "1") (pinfunction "VCC_1") (pintype "passive"))
      (node (ref "B2") (pin "1") (pinfunction "VCC_1") (pintype "passive"))
      (node (ref "B3") (pin "1") (pinfunction "VCC_1") (pintype "passive"))
      (node (ref "B4") (pin "1") (pinfunction "VCC_1") (pintype "passive"))
      (node (ref "C3") (pin "1") (pinfunction "1_1") (pintype "passive"))
      (node (ref "C4") (pin "1") (pinfunction "1_1") (pintype "passive"))
      (node (ref "C5") (pin "1") (pinfunction "1_1") (pintype "passive"))
      (node (ref "C6") (pin "1") (pinfunction "1_1") (pintype "passive"))
      (node (ref "FP3") (pin "1") (pintype "passive"))
      (node (ref "TP13") (pin "1") (pintype "passive"))
    )
    (net (code "82") (name "ISO_GND") (class "Default")
      (node (ref "B1") (pin "2") (pinfunction "GND_2") (pintype "passive"))
      (node (ref "B2") (pin "2") (pinfunction "GND_2") (pintype "passive"))
      (node (ref "B3") (pin "2") (pinfunction "GND_2") (pintype "passive"))
      (node (ref "B4") (pin "2") (pinfunction "GND_2") (pintype "passive"))
      (node (ref "C3") (pin "2") (pinfunction "2_2") (pintype "passive"))
      (node (ref "C4") (pin "2") (pinfunction "2_2") (pintype "passive"))
      (node (ref "C5") (pin "2") (pinfunction "2_2") (pintype "passive"))
      (node (ref "C6") (pin "2") (pinfunction "2_2") (pintype "passive"))
      (node (ref "R10") (pin "1") (pintype "passive"))
      (node (ref "R11") (pin "1") (pintype "passive"))
      (node (ref "R12") (pin "1") (pintype "passive"))
      (node (ref "R13") (pin "1") (pintype "passive"))
      (node (ref "TP31") (pin "1") (pintype "passive"))
      (node (ref "TP32") (pin "1") (pintype "passive"))
      (node (ref "TP33") (pin "1") (pintype "passive"))
      (node (ref "TP34") (pin "1") (pintype "passive"))
    )
    (net (code "83") (name "Net-(X1-Shield)") (class "Default")
      (node (ref "C1") (pin "1") (pinfunction "1_1") (pintype "passive"))
      (node (ref "R3") (pin "1") (pintype "passive"))
      (node (ref "X1") (pin "SH") (pinfunction "Shield_SH") (pintype "passive"))
    )
    (net (code "84") (name "Net-(X4-Shield)") (class "Default")
      (node (ref "C2") (pin "1") (pinfunction "1_1") (pintype "passive"))
      (node (ref "R9") (pin "1") (pintype "passive"))
      (node (ref "X4") (pin "SH") (pinfunction "Shield_SH") (pintype "passive"))
    )
    (net (code "85") (name "unconnected-(TP2-Pad1)") (class "Default")
      (node (ref "TP2") (pin "1") (pintype "passive"))
    )
    (net (code "86") (name "unconnected-(TP4-Pad1)") (class "Default")
      (node (ref "TP4") (pin "1") (pintype "passive"))
    )
    (net (code "87") (name "unconnected-(TP6-Pad1)") (class "Default")
      (node (ref "TP6") (pin "1") (pintype "passive"))
    )
    (net (code "88") (name "unconnected-(TP8-Pad1)") (class "Default")
      (node (ref "TP8") (pin "1") (pintype "passive"))
    )
    (net (code "89") (name "unconnected-(TP11-Pad1)") (class "Default")
      (node (ref "TP11") (pin "1") (pintype "passive"))
    )
    (net (code "90") (name "unconnected-(TP12-Pad1)") (class "Default")
      (node (ref "TP12") (pin "1") (pintype "passive"))
    )
    (net (code "91") (name "unconnected-(TP15-Pad1)") (class "Default")
      (node (ref "TP15") (pin "1") (pintype "passive"))
    )
    (net (code "92") (name "unconnected-(TP20-Pad1)") (class "Default")
      (node (ref "TP20") (pin "1") (pintype "passive"))
    )
    (net (code "93") (name "unconnected-(TP21-Pad1)") (class "Default")
      (node (ref "TP21") (pin "1") (pintype "passive"))
    )
    (net (code "94") (name "unconnected-(TP22-Pad1)") (class "Default")
      (node (ref "TP22") (pin "1") (pintype "passive"))
    )
    (net (code "95") (name "unconnected-(TP23-Pad1)") (class "Default")
      (node (ref "TP23") (pin "1") (pintype "passive"))
    )
    (net (code "96") (name "unconnected-(TP24-Pad1)") (class "Default")
      (node (ref "TP24") (pin "1") (pintype "passive"))
    )
    (net (code "97") (name "unconnected-(TP25-Pad1)") (class "Default")
      (node (ref "TP25") (pin "1") (pintype "passive"))
    )
    (net (code "98") (name "unconnected-(TP26-Pad1)") (class "Default")
      (node (ref "TP26") (pin "1") (pintype "passive"))
    )
    (net (code "99") (name "unconnected-(TP27-Pad1)") (class "Default")
      (node (ref "TP27") (pin "1") (pintype "passive"))
    )
    (net (code "100") (name "unconnected-(TP28-Pad1)") (class "Default")
      (node (ref "TP28") (pin "1") (pintype "passive"))
    )
    (net (code "101") (name "unconnected-(TP29-Pad1)") (class "Default")
      (node (ref "TP29") (pin "1") (pintype "passive"))
    )
    (net (code "102") (name "unconnected-(TP30-Pad1)") (class "Default")
      (node (ref "TP30") (pin "1") (pintype "passive"))
    )
    (net (code "103") (name "unconnected-(VD1-PadAN)") (class "Default")
      (node (ref "VD1") (pin "AN") (pintype "passive"))
    )
    (net (code "104") (name "unconnected-(VD1-PadCA)") (class "Default")
      (node (ref "VD1") (pin "CA") (pintype "passive"))
    )
  )
)
